# USBReallyTinyISPv1.net
KiCad netlist of a schematic drawn in EAGLE
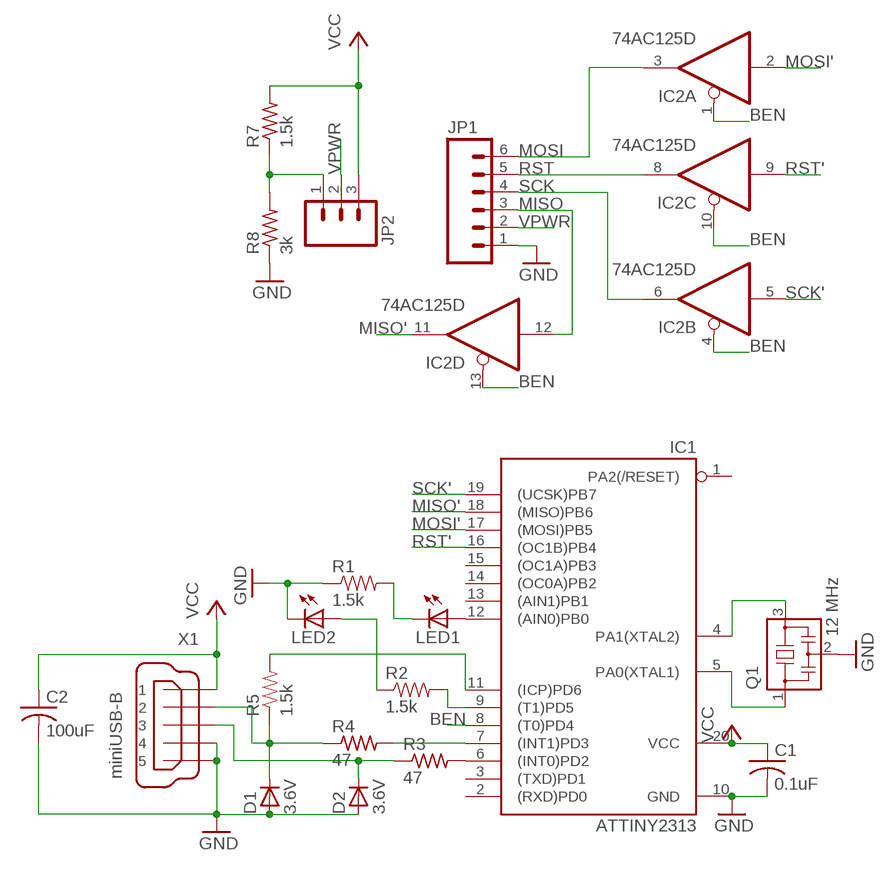
[diagram p0: schematic, sheet 1]

(export (version "E")
  (design (tool "Eeschema 10.0.6"))
  (components
    (comp (ref "C1")
      (value "0.1uF")
      (footprint "eagle-import:C0805")
      (libsource (lib "eagle-import") (part "C-USC0805"))
    )
    (comp (ref "C2")
      (value "100uF")
      (footprint "eagle-import:C1206")
      (libsource (lib "eagle-import") (part "resistor_C-USC1206"))
    )
    (comp (ref "D1")
      (value "3.6V")
      (footprint "eagle-import:SOD3718X135N")
      (libsource (lib "eagle-import") (part "DIODE_SOD-123"))
    )
    (comp (ref "D2")
      (value "3.6V")
      (footprint "eagle-import:SOD3718X135N")
      (libsource (lib "eagle-import") (part "DIODE_SOD-123"))
    )
    (comp (ref "IC1")
      (value "ATTINY2313")
      (footprint "eagle-import:SO20L$")
      (libsource (lib "eagle-import") (part "TINY2313-S"))
    )
    (comp (ref "IC2")
      (value "74AC125D")
      (footprint "eagle-import:SO14")
      (libsource (lib "eagle-import") (part "74125DAC"))
    )
    (comp (ref "JP1")
      (value "M06SILK_FEMALE_PTH")
      (footprint "eagle-import:1X06")
      (libsource (lib "eagle-import") (part "M06SILK_FEMALE_PTH"))
    )
    (comp (ref "JP2")
      (value "M03-SHORTEDPTH")
      (footprint "eagle-import:1X03")
      (libsource (lib "eagle-import") (part "M03-SHORTEDPTH"))
    )
    (comp (ref "LED1")
      (value "LEDSML0805")
      (footprint "eagle-import:SML0805")
      (libsource (lib "eagle-import") (part "LEDSML0805"))
    )
    (comp (ref "LED2")
      (value "LEDSML0805")
      (footprint "eagle-import:SML0805")
      (libsource (lib "eagle-import") (part "LEDSML0805"))
    )
    (comp (ref "Q1")
      (value "12 MHz")
      (footprint "eagle-import:CSTCR6M")
      (fields (field (name "MPN") "CSTCR6M00G53-R0"))
      (libsource (lib "eagle-import") (part "CSTCR6M00G53Z"))
    )
    (comp (ref "R1")
      (value "1.5k")
      (footprint "eagle-import:1206")
      (libsource (lib "eagle-import") (part "RESISTOR1206"))
    )
    (comp (ref "R2")
      (value "1.5k")
      (footprint "eagle-import:1206")
      (libsource (lib "eagle-import") (part "RESISTOR1206"))
    )
    (comp (ref "R3")
      (value "47")
      (footprint "eagle-import:R0805")
      (libsource (lib "eagle-import") (part "R-US_R0805"))
    )
    (comp (ref "R4")
      (value "47")
      (footprint "eagle-import:R0805")
      (libsource (lib "eagle-import") (part "R-US_R0805"))
    )
    (comp (ref "R5")
      (value "1.5k")
      (footprint "eagle-import:1206")
      (libsource (lib "eagle-import") (part "RESISTOR1206"))
    )
    (comp (ref "R7")
      (value "1.5k")
      (footprint "eagle-import:R0805")
      (libsource (lib "eagle-import") (part "R-US_R0805"))
    )
    (comp (ref "R8")
      (value "3k")
      (footprint "eagle-import:R0805")
      (libsource (lib "eagle-import") (part "R-US_R0805"))
    )
    (comp (ref "X1")
      (value "miniUSB-B")
      (footprint "eagle-import:UX60A-MB-5ST")
      (libsource (lib "eagle-import") (part "MINI-USB-UX60A-MB-5ST"))
    )
  )
  (nets
    (net (code "1") (name "/BEN") (class "Default")
      (node (ref "IC1") (pin "8") (pinfunction "(T0)PD4_8") (pintype "bidirectional"))
      (node (ref "IC2") (pin "1") (pinfunction "OE_1") (pintype "input"))
      (node (ref "IC2") (pin "10") (pinfunction "OE_10") (pintype "input"))
      (node (ref "IC2") (pin "13") (pinfunction "OE_13") (pintype "input"))
      (node (ref "IC2") (pin "4") (pinfunction "OE_4") (pintype "input"))
    )
    (net (code "2") (name "/MISO") (class "Default")
      (node (ref "IC2") (pin "12") (pinfunction "I_12") (pintype "input"))
      (node (ref "JP1") (pin "3") (pinfunction "3_3") (pintype "passive"))
    )
    (net (code "3") (name "/MISO'") (class "Default")
      (node (ref "IC1") (pin "18") (pinfunction "(MISO)PB6_18") (pintype "bidirectional"))
      (node (ref "IC2") (pin "11") (pinfunction "O_11") (pintype "tri_state"))
    )
    (net (code "4") (name "/MOSI") (class "Default")
      (node (ref "IC2") (pin "3") (pinfunction "O_3") (pintype "tri_state"))
      (node (ref "JP1") (pin "6") (pinfunction "6_6") (pintype "passive"))
    )
    (net (code "5") (name "/MOSI'") (class "Default")
      (node (ref "IC1") (pin "17") (pinfunction "(MOSI)PB5_17") (pintype "bidirectional"))
      (node (ref "IC2") (pin "2") (pinfunction "I_2") (pintype "input"))
    )
    (net (code "6") (name "/RST") (class "Default")
      (node (ref "IC2") (pin "8") (pinfunction "O_8") (pintype "tri_state"))
      (node (ref "JP1") (pin "5") (pinfunction "5_5") (pintype "passive"))
    )
    (net (code "7") (name "/RST'") (class "Default")
      (node (ref "IC1") (pin "16") (pinfunction "(OC1B)PB4_16") (pintype "bidirectional"))
      (node (ref "IC2") (pin "9") (pinfunction "I_9") (pintype "input"))
    )
    (net (code "8") (name "/SCK") (class "Default")
      (node (ref "IC2") (pin "6") (pinfunction "O_6") (pintype "tri_state"))
      (node (ref "JP1") (pin "4") (pinfunction "4_4") (pintype "passive"))
    )
    (net (code "9") (name "/SCK'") (class "Default")
      (node (ref "IC1") (pin "19") (pinfunction "(UCSK)PB7_19") (pintype "bidirectional"))
      (node (ref "IC2") (pin "5") (pinfunction "I_5") (pintype "input"))
    )
    (net (code "10") (name "/VPWR") (class "Default")
      (node (ref "JP1") (pin "2") (pinfunction "2_2") (pintype "passive"))
      (node (ref "JP2") (pin "2") (pinfunction "2_2") (pintype "passive"))
    )
    (net (code "11") (name "GND") (class "Default")
      (node (ref "C1") (pin "2") (pinfunction "2_2") (pintype "passive"))
      (node (ref "C2") (pin "2") (pinfunction "2_2") (pintype "passive"))
      (node (ref "D1") (pin "A") (pinfunction "A_A") (pintype "passive"))
      (node (ref "D2") (pin "A") (pinfunction "A_A") (pintype "passive"))
      (node (ref "IC1") (pin "10") (pinfunction "GND_10") (pintype "power_in"))
      (node (ref "JP1") (pin "1") (pinfunction "1_1") (pintype "passive"))
      (node (ref "LED2") (pin "C") (pinfunction "C_C") (pintype "passive"))
      (node (ref "Q1") (pin "2") (pinfunction "2_2") (pintype "passive"))
      (node (ref "R1") (pin "1") (pinfunction "1_1") (pintype "passive"))
      (node (ref "R8") (pin "1") (pinfunction "1_1") (pintype "passive"))
      (node (ref "X1") (pin "4") (pinfunction "4_4") (pintype "input"))
      (node (ref "X1") (pin "5") (pinfunction "5_5") (pintype "input"))
    )
    (net (code "12") (name "Net-(D1-PadK)") (class "Default")
      (node (ref "D1") (pin "K") (pinfunction "K_K") (pintype "passive"))
      (node (ref "R4") (pin "1") (pinfunction "1_1") (pintype "passive"))
      (node (ref "R5") (pin "1") (pinfunction "1_1") (pintype "passive"))
      (node (ref "X1") (pin "2") (pinfunction "2_2") (pintype "input"))
    )
    (net (code "13") (name "Net-(D2-PadK)") (class "Default")
      (node (ref "D2") (pin "K") (pinfunction "K_K") (pintype "passive"))
      (node (ref "R3") (pin "1") (pinfunction "1_1") (pintype "passive"))
      (node (ref "X1") (pin "3") (pinfunction "3_3") (pintype "input"))
    )
    (net (code "14") (name "Net-(IC1-(AIN0)PB0)") (class "Default")
      (node (ref "IC1") (pin "12") (pinfunction "(AIN0)PB0_12") (pintype "bidirectional"))
      (node (ref "LED1") (pin "A") (pinfunction "A_A") (pintype "passive"))
    )
    (net (code "15") (name "Net-(IC1-(ICP)PD6)") (class "Default")
      (node (ref "IC1") (pin "11") (pinfunction "(ICP)PD6_11") (pintype "bidirectional"))
      (node (ref "R5") (pin "2") (pinfunction "2_2") (pintype "passive"))
    )
    (net (code "16") (name "Net-(IC1-(INT0)PD2)") (class "Default")
      (node (ref "IC1") (pin "6") (pinfunction "(INT0)PD2_6") (pintype "bidirectional"))
      (node (ref "R3") (pin "2") (pinfunction "2_2") (pintype "passive"))
    )
    (net (code "17") (name "Net-(IC1-(INT1)PD3)") (class "Default")
      (node (ref "IC1") (pin "7") (pinfunction "(INT1)PD3_7") (pintype "bidirectional"))
      (node (ref "R4") (pin "2") (pinfunction "2_2") (pintype "passive"))
    )
    (net (code "18") (name "Net-(IC1-(T1)PD5)") (class "Default")
      (node (ref "IC1") (pin "9") (pinfunction "(T1)PD5_9") (pintype "bidirectional"))
      (node (ref "R2") (pin "2") (pinfunction "2_2") (pintype "passive"))
    )
    (net (code "19") (name "Net-(IC1-PA0(XTAL1))") (class "Default")
      (node (ref "IC1") (pin "5") (pinfunction "PA0(XTAL1)_5") (pintype "bidirectional"))
      (node (ref "Q1") (pin "1") (pinfunction "1_1") (pintype "passive"))
    )
    (net (code "20") (name "Net-(IC1-PA1(XTAL2))") (class "Default")
      (node (ref "IC1") (pin "4") (pinfunction "PA1(XTAL2)_4") (pintype "bidirectional"))
      (node (ref "Q1") (pin "3") (pinfunction "3_3") (pintype "passive"))
    )
    (net (code "21") (name "Net-(JP2-Pad1)") (class "Default")
      (node (ref "JP2") (pin "1") (pinfunction "1_1") (pintype "passive"))
      (node (ref "R7") (pin "1") (pinfunction "1_1") (pintype "passive"))
      (node (ref "R8") (pin "2") (pinfunction "2_2") (pintype "passive"))
    )
    (net (code "22") (name "Net-(LED1-PadC)") (class "Default")
      (node (ref "LED1") (pin "C") (pinfunction "C_C") (pintype "passive"))
      (node (ref "R1") (pin "2") (pinfunction "2_2") (pintype "passive"))
    )
    (net (code "23") (name "Net-(LED2-PadA)") (class "Default")
      (node (ref "LED2") (pin "A") (pinfunction "A_A") (pintype "passive"))
      (node (ref "R2") (pin "1") (pinfunction "1_1") (pintype "passive"))
    )
    (net (code "24") (name "VCC") (class "Default")
      (node (ref "C1") (pin "1") (pinfunction "1_1") (pintype "passive"))
      (node (ref "C2") (pin "1") (pinfunction "1_1") (pintype "passive"))
      (node (ref "IC1") (pin "20") (pinfunction "VCC_20") (pintype "power_in"))
      (node (ref "JP2") (pin "3") (pinfunction "3_3") (pintype "passive"))
      (node (ref "R7") (pin "2") (pinfunction "2_2") (pintype "passive"))
      (node (ref "X1") (pin "1") (pinfunction "1_1") (pintype "input"))
    )
    (net (code "25") (name "unconnected-(IC1-(AIN1)PB1-Pad13)") (class "Default")
      (node (ref "IC1") (pin "13") (pinfunction "(AIN1)PB1_13") (pintype "bidirectional"))
    )
    (net (code "26") (name "unconnected-(IC1-(OC0A)PB2-Pad14)") (class "Default")
      (node (ref "IC1") (pin "14") (pinfunction "(OC0A)PB2_14") (pintype "bidirectional"))
    )
    (net (code "27") (name "unconnected-(IC1-(OC1A)PB3-Pad15)") (class "Default")
      (node (ref "IC1") (pin "15") (pinfunction "(OC1A)PB3_15") (pintype "bidirectional"))
    )
    (net (code "28") (name "unconnected-(IC1-(RXD)PD0-Pad2)") (class "Default")
      (node (ref "IC1") (pin "2") (pinfunction "(RXD)PD0_2") (pintype "bidirectional"))
    )
    (net (code "29") (name "unconnected-(IC1-(TXD)PD1-Pad3)") (class "Default")
      (node (ref "IC1") (pin "3") (pinfunction "(TXD)PD1_3") (pintype "bidirectional"))
    )
    (net (code "30") (name "unconnected-(IC1-PA2({slash}RESET)-Pad1)") (class "Default")
      (node (ref "IC1") (pin "1") (pinfunction "PA2(/RESET)_1") (pintype "input"))
    )
  )
)
